# AMU-S02-V00-PSU3V3.net
KiCad netlist of a schematic drawn in Altium Designer
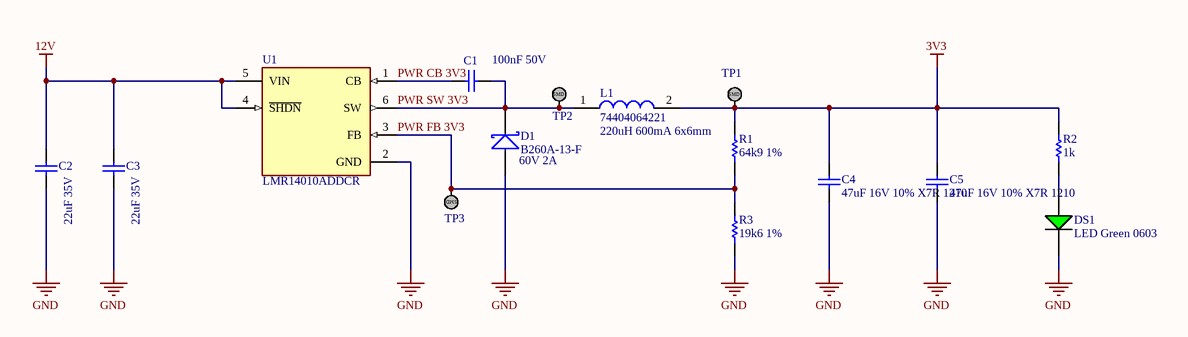
[diagram p0: AMU-S02-V00-PSU3V3.SchDoc]

(export (version "E")
  (design (tool "Eeschema 10.0.6"))
  (components
    (comp (ref "C1")
      (value "100nF 50V")
      (footprint "Cap_Ceramic_0603")
      (description "Capacitor, Ceramic, SMD, 100nF, 50V, 5%, X7R, 0603")
      (libsource (lib "StandardCapacitors") (part "100nF 50V 5% X7R 0603"))
    )
    (comp (ref "C2")
      (value "22uF 35V")
      (footprint "Cap_Ceramic_1206")
      (description "22µF ±20% 35V Ceramic Capacitor X5R 1206 (3216 Metric)")
      (libsource (lib "StandardCapacitors") (part "22uF 35V 20% X5R 1206"))
    )
    (comp (ref "C3")
      (value "22uF 35V")
      (footprint "Cap_Ceramic_1206")
      (description "22µF ±20% 35V Ceramic Capacitor X5R 1206 (3216 Metric)")
      (libsource (lib "StandardCapacitors") (part "22uF 35V 20% X5R 1206"))
    )
    (comp (ref "C4")
      (value "47uF 16V 10% X7R 1210")
      (footprint "Cap_Ceramic_1210")
      (description "Capacitor, Ceramic, SMD, 47uF, 16V, 5%, X7R, 1210")
      (libsource (lib "StandardCapacitors") (part "47uF 16V 10% X7R 1210"))
    )
    (comp (ref "C5")
      (value "47uF 16V 10% X7R 1210")
      (footprint "Cap_Ceramic_1210")
      (description "Capacitor, Ceramic, SMD, 47uF, 16V, 5%, X7R, 1210")
      (libsource (lib "StandardCapacitors") (part "47uF 16V 10% X7R 1210"))
    )
    (comp (ref "D1")
      (value "B260A-13-F")
      (footprint "SMA")
      (description "Diode, Schottky Barrier Rectifier, 60 V, 2 A, B260A-13-F")
      (libsource (lib "QUTMS_DiodeLibrary") (part "B260A-13-F"))
    )
    (comp (ref "DS1")
      (value "LED Green 0603")
      (footprint "LED GREEN 0603")
      (libsource (lib "QUTMS_LEDLibrary") (part "LED Green 0603"))
    )
    (comp (ref "L1")
      (value "74404064221")
      (footprint "Inductor_6x6mm")
      (description "FIXED IND 220UH 660MA 850 MOHM")
      (libsource (lib "QUTMS_InductorLibrary") (part "74404064221"))
    )
    (comp (ref "R1")
      (value "64k9 1%")
      (footprint "Res_ThinFilm_0603")
      (description "Resistor, SMD, 64k9, 0.1W, 5%, 0603")
      (libsource (lib "StandardResistors") (part "64k9 1% 0603"))
    )
    (comp (ref "R2")
      (value "1k")
      (footprint "Res_ThinFilm_0603")
      (description "Resistor, SMD, 1k, 0.1W, 5%, 0603")
      (libsource (lib "StandardResistors") (part "1k 5% 0603"))
    )
    (comp (ref "R3")
      (value "19k6 1%")
      (footprint "Res_ThinFilm_0603")
      (description "Resistor, SMD, 19k6, 0.1W, 5%, 0603")
      (libsource (lib "StandardResistors") (part "19k6 1% 0603"))
    )
    (comp (ref "TP1")
      (value "TestPoint_SMD")
      (footprint "TestPointSMD")
      (libsource (lib "StandardTest") (part "TestPoint_SMD"))
    )
    (comp (ref "TP2")
      (value "TestPoint_SMD")
      (footprint "TestPointSMD")
      (libsource (lib "StandardTest") (part "TestPoint_SMD"))
    )
    (comp (ref "TP3")
      (value "TestPoint_SMD")
      (footprint "TestPointSMD")
      (libsource (lib "StandardTest") (part "TestPoint_SMD"))
    )
    (comp (ref "U1")
      (value "LMR14010ADDCR")
      (footprint "FP-DDC0006A-MFG")
      (description "IC REG BUCK ADJ 1A TSOT23-6")
      (fields
        (field (name "MANUFACTURER") "Texas Instruments")
        (field (name "OCTOPART") "https://octopart.com/lmr14010addcr-texas+instruments-90753290")
      )
      (libsource (lib "Altium Content Vault") (part "248534993f007311ab4e1890f26e637"))
    )
  )
  (nets
    (net (code "1") (name "/PWR CB 3V3") (class "Default")
      (node (ref "C1") (pin "1") (pinfunction "1_1") (pintype "passive"))
      (node (ref "U1") (pin "1") (pinfunction "CB_1") (pintype "input"))
    )
    (net (code "2") (name "/PWR FB 3V3") (class "Default")
      (node (ref "R1") (pin "1") (pinfunction "1_1") (pintype "passive"))
      (node (ref "R3") (pin "2") (pinfunction "2_2") (pintype "passive"))
      (node (ref "TP3") (pin "1") (pinfunction "1_1") (pintype "passive"))
      (node (ref "U1") (pin "3") (pinfunction "FB_3") (pintype "input"))
    )
    (net (code "3") (name "/PWR SW 3V3") (class "Default")
      (node (ref "C1") (pin "2") (pinfunction "2_2") (pintype "passive"))
      (node (ref "D1") (pin "K") (pinfunction "K_K") (pintype "passive"))
      (node (ref "L1") (pin "1") (pinfunction "1_1") (pintype "passive"))
      (node (ref "TP2") (pin "1") (pinfunction "1_1") (pintype "passive"))
      (node (ref "U1") (pin "6") (pinfunction "SW_6") (pintype "output"))
    )
    (net (code "4") (name "3V3") (class "Default")
      (node (ref "C4") (pin "2") (pinfunction "2_2") (pintype "passive"))
      (node (ref "C5") (pin "2") (pinfunction "2_2") (pintype "passive"))
      (node (ref "L1") (pin "2") (pinfunction "2_2") (pintype "passive"))
      (node (ref "R1") (pin "2") (pinfunction "2_2") (pintype "passive"))
      (node (ref "R2") (pin "2") (pinfunction "2_2") (pintype "passive"))
      (node (ref "TP1") (pin "1") (pinfunction "1_1") (pintype "passive"))
    )
    (net (code "5") (name "12V") (class "Default")
      (node (ref "C2") (pin "2") (pinfunction "2_2") (pintype "passive"))
      (node (ref "C3") (pin "2") (pinfunction "2_2") (pintype "passive"))
      (node (ref "U1") (pin "4") (pinfunction "~{SHDN}_4") (pintype "input"))
      (node (ref "U1") (pin "5") (pinfunction "VIN_5") (pintype "power_in"))
    )
    (net (code "6") (name "GND") (class "Default")
      (node (ref "C2") (pin "1") (pinfunction "1_1") (pintype "passive"))
      (node (ref "C3") (pin "1") (pinfunction "1_1") (pintype "passive"))
      (node (ref "C4") (pin "1") (pinfunction "1_1") (pintype "passive"))
      (node (ref "C5") (pin "1") (pinfunction "1_1") (pintype "passive"))
      (node (ref "D1") (pin "A") (pinfunction "A_A") (pintype "passive"))
      (node (ref "DS1") (pin "2") (pinfunction "C_2") (pintype "passive"))
      (node (ref "R3") (pin "1") (pinfunction "1_1") (pintype "passive"))
      (node (ref "U1") (pin "2") (pinfunction "GND_2") (pintype "power_in"))
    )
    (net (code "7") (name "Net-(DS1-A)") (class "Default")
      (node (ref "DS1") (pin "1") (pinfunction "A_1") (pintype "passive"))
      (node (ref "R2") (pin "1") (pinfunction "1_1") (pintype "passive"))
    )
  )
)
